# tick-mk-4_7.net
KiCad netlist of a schematic drawn in EAGLE
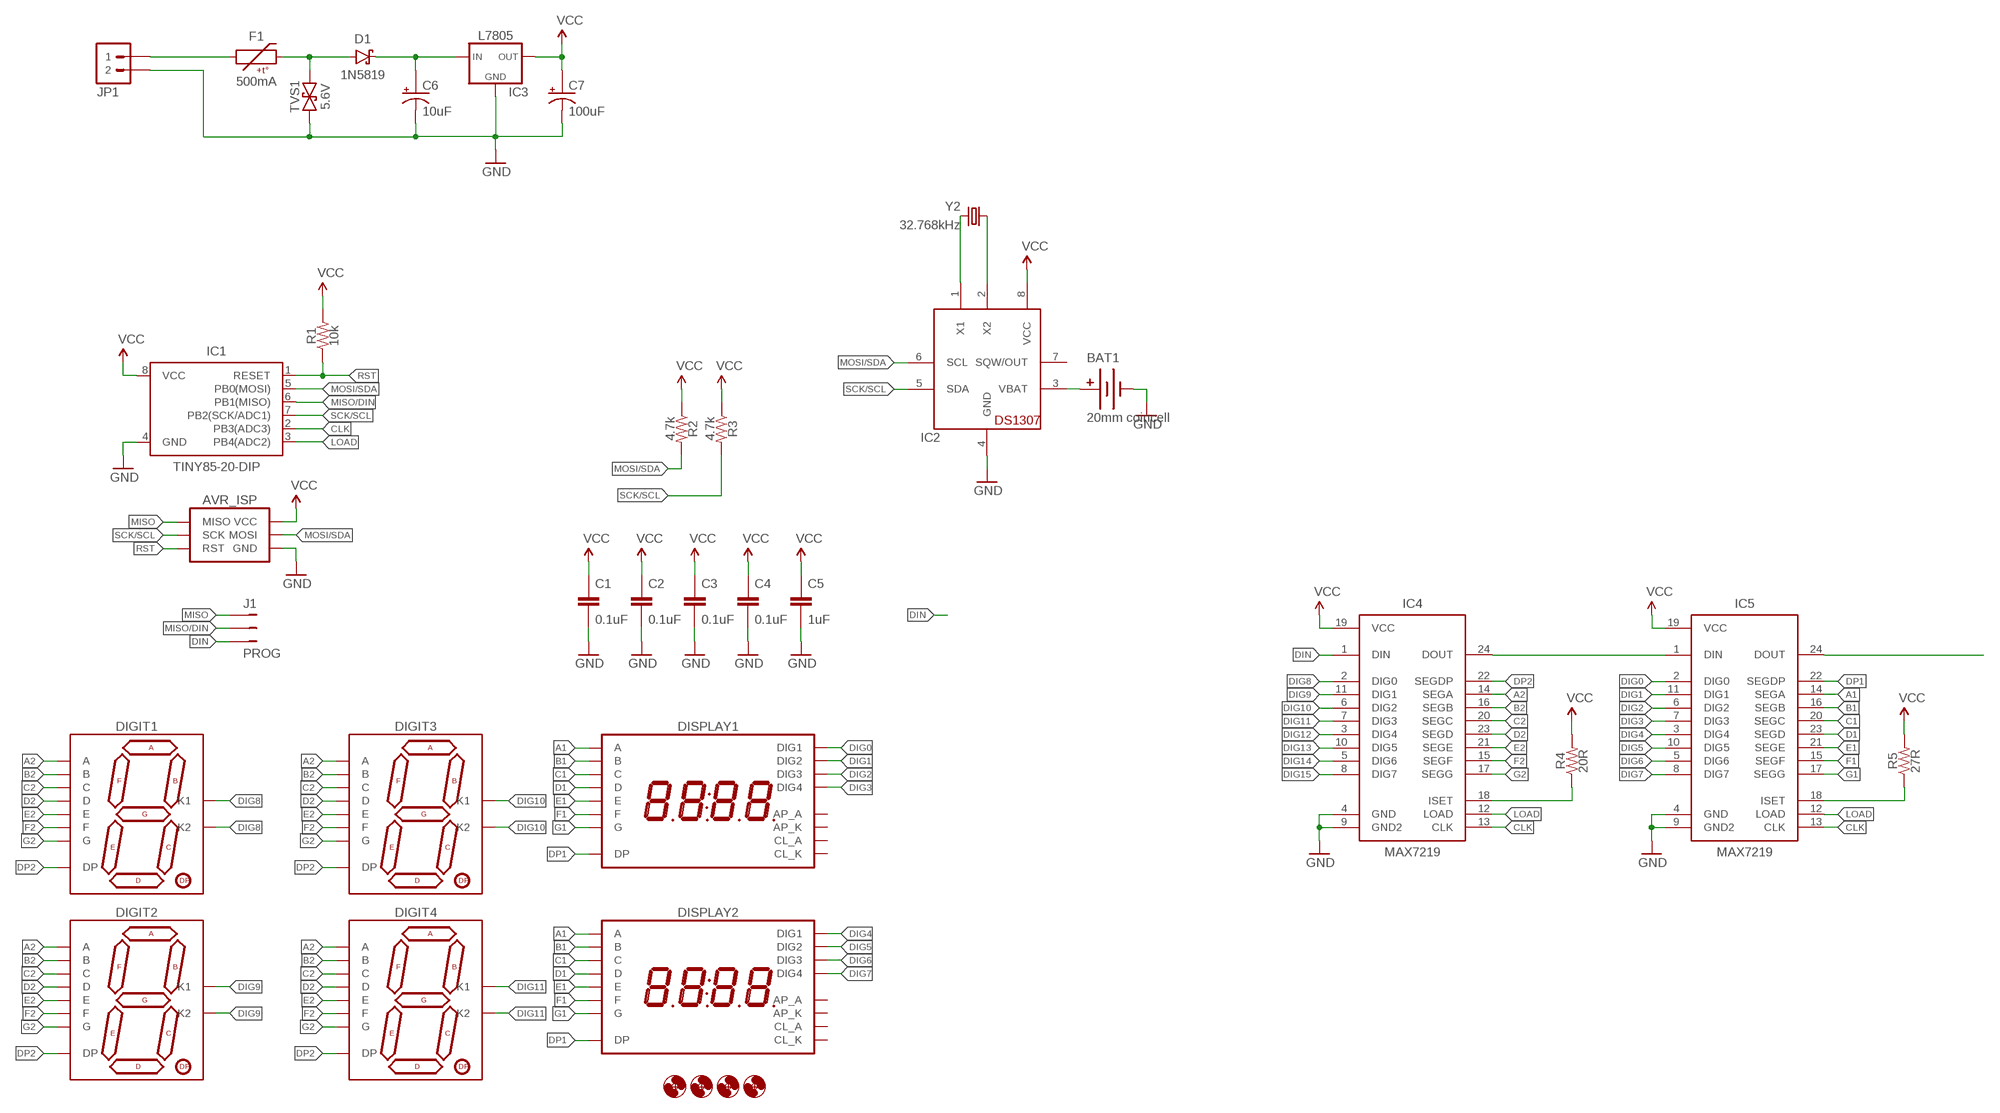
[diagram p0: schematic, sheet 1]

(export (version "E")
  (design (tool "Eeschema 10.0.6"))
  (components
    (comp (ref "AVR_ISP")
      (value "AVR_SPI_PRG_6PTH")
      (footprint "eagle-import:2X3")
      (libsource (lib "eagle-import") (part "AVR_SPI_PRG_6PTH"))
    )
    (comp (ref "BAT1")
      (value "20mm coincell")
      (footprint "eagle-import:BATTCON_20MM_MINE")
      (libsource (lib "eagle-import") (part "BATTERY20MMSMD-MINE"))
    )
    (comp (ref "C1")
      (value "0.1uF")
      (footprint "eagle-import:C025-024X044")
      (libsource (lib "eagle-import") (part "CAPACITOR-CERAMIC025-024X044"))
    )
    (comp (ref "C2")
      (value "0.1uF")
      (footprint "eagle-import:C025-024X044")
      (libsource (lib "eagle-import") (part "CAPACITOR-CERAMIC025-024X044"))
    )
    (comp (ref "C3")
      (value "0.1uF")
      (footprint "eagle-import:C025-024X044")
      (libsource (lib "eagle-import") (part "CAPACITOR-CERAMIC025-024X044"))
    )
    (comp (ref "C4")
      (value "0.1uF")
      (footprint "eagle-import:C025-024X044")
      (libsource (lib "eagle-import") (part "CAPACITOR-CERAMIC025-024X044"))
    )
    (comp (ref "C5")
      (value "1uF")
      (footprint "eagle-import:C025-024X044")
      (libsource (lib "eagle-import") (part "CAPACITOR-CERAMIC025-024X044"))
    )
    (comp (ref "C6")
      (value "10uF")
      (footprint "eagle-import:E2-5")
      (libsource (lib "eagle-import") (part "CAPACITOR-POLARIZEDE2-5"))
    )
    (comp (ref "C7")
      (value "100uF")
      (footprint "eagle-import:E2,5-6")
      (libsource (lib "eagle-import") (part "CAPACITOR-POLARIZEDE2.5-6"))
    )
    (comp (ref "D1")
      (value "1N5819")
      (footprint "eagle-import:DIODE-10.16MM")
      (libsource (lib "eagle-import") (part "DIODE-SCHOTTKYPTH-10.16MM"))
    )
    (comp (ref "DIGIT1")
      (value "7SEG_1DIGPTH-25.4MM-BARE")
      (footprint "eagle-import:7SEG_1DIG_25.4MM_NOSILK")
      (libsource (lib "eagle-import") (part "7SEG_1DIGPTH-25.4MM-BARE"))
    )
    (comp (ref "DIGIT2")
      (value "7SEG_1DIGPTH-25.4MM-BARE")
      (footprint "eagle-import:7SEG_1DIG_25.4MM_NOSILK")
      (libsource (lib "eagle-import") (part "7SEG_1DIGPTH-25.4MM-BARE"))
    )
    (comp (ref "DIGIT3")
      (value "7SEG_1DIGPTH-25.4MM-BARE")
      (footprint "eagle-import:7SEG_1DIG_25.4MM_NOSILK")
      (libsource (lib "eagle-import") (part "7SEG_1DIGPTH-25.4MM-BARE"))
    )
    (comp (ref "DIGIT4")
      (value "7SEG_1DIGPTH-25.4MM-BARE")
      (footprint "eagle-import:7SEG_1DIG_25.4MM_NOSILK")
      (libsource (lib "eagle-import") (part "7SEG_1DIGPTH-25.4MM-BARE"))
    )
    (comp (ref "DISPLAY1")
      (value "7SEG_4DIGIT_COLON_APOS")
      (footprint "eagle-import:7SEG_4DIG_10MM")
      (libsource (lib "eagle-import") (part "7SEG_4DIGIT_COLON_APOS"))
    )
    (comp (ref "DISPLAY2")
      (value "7SEG_4DIGIT_COLON_APOS")
      (footprint "eagle-import:7SEG_4DIG_10MM")
      (libsource (lib "eagle-import") (part "7SEG_4DIGIT_COLON_APOS"))
    )
    (comp (ref "F1")
      (value "500mA")
      (footprint "eagle-import:PTC-PTH-5.08MM")
      (libsource (lib "eagle-import") (part "PTCPTH-5.08MM"))
    )
    (comp (ref "H1")
      (value "HOLE#2")
      (footprint "eagle-import:HOLE-#2")
      (libsource (lib "eagle-import") (part "HOLE#2"))
    )
    (comp (ref "H2")
      (value "HOLE#2")
      (footprint "eagle-import:HOLE-#2")
      (libsource (lib "eagle-import") (part "HOLE#2"))
    )
    (comp (ref "H3")
      (value "HOLE#2")
      (footprint "eagle-import:HOLE-#2")
      (libsource (lib "eagle-import") (part "HOLE#2"))
    )
    (comp (ref "H4")
      (value "HOLE#2")
      (footprint "eagle-import:HOLE-#2")
      (libsource (lib "eagle-import") (part "HOLE#2"))
    )
    (comp (ref "IC1")
      (value "TINY85-20-DIP")
      (footprint "eagle-import:DIP08")
      (libsource (lib "eagle-import") (part "ATTINY45TINY85-20-DIP"))
    )
    (comp (ref "IC2")
      (value "DS1307")
      (footprint "eagle-import:DIL08")
      (libsource (lib "eagle-import") (part "DS1307"))
    )
    (comp (ref "IC3")
      (value "L7805")
      (footprint "eagle-import:TO220-IGO-THERMPAD")
      (libsource (lib "eagle-import") (part "V_REG_78XXTO-220-THERMPAD"))
    )
    (comp (ref "IC4")
      (value "MAX7219")
      (footprint "eagle-import:SO24W")
      (libsource (lib "eagle-import") (part "MAX7219SOIC-W"))
    )
    (comp (ref "IC5")
      (value "MAX7219")
      (footprint "eagle-import:SO24W")
      (libsource (lib "eagle-import") (part "MAX7219SOIC-W"))
    )
    (comp (ref "J1")
      (value "PROG")
      (footprint "eagle-import:1X03")
      (libsource (lib "eagle-import") (part "JUMPER-PTH-3-NO"))
    )
    (comp (ref "JP1")
      (value "M02JST-XH-VERT")
      (footprint "eagle-import:JST-2-XH-VERT-PTH")
      (libsource (lib "eagle-import") (part "M02JST-XH-VERT"))
    )
    (comp (ref "R1")
      (value "10k")
      (footprint "eagle-import:RESISTOR-AXIAL-PTH-7.62MM")
      (libsource (lib "eagle-import") (part "RESISTORPTH-AXIAL-7.62MM"))
    )
    (comp (ref "R2")
      (value "4.7k")
      (footprint "eagle-import:RESISTOR-AXIAL-PTH-7.62MM")
      (libsource (lib "eagle-import") (part "RESISTORPTH-AXIAL-7.62MM"))
    )
    (comp (ref "R3")
      (value "4.7k")
      (footprint "eagle-import:RESISTOR-AXIAL-PTH-7.62MM")
      (libsource (lib "eagle-import") (part "RESISTORPTH-AXIAL-7.62MM"))
    )
    (comp (ref "R4")
      (value "20R")
      (footprint "eagle-import:RESISTOR-AXIAL-PTH-7.62MM")
      (libsource (lib "eagle-import") (part "RESISTORPTH-AXIAL-7.62MM"))
    )
    (comp (ref "R5")
      (value "27R")
      (footprint "eagle-import:RESISTOR-AXIAL-PTH-7.62MM")
      (libsource (lib "eagle-import") (part "RESISTORPTH-AXIAL-7.62MM"))
    )
    (comp (ref "TVS1")
      (value "5.6V")
      (footprint "eagle-import:DO-41-TVS-BI-10.16MM")
      (libsource (lib "eagle-import") (part "TVSDO-41-10.16MM"))
    )
    (comp (ref "Y2")
      (value "32.768kHz")
      (footprint "eagle-import:TC26H")
      (libsource (lib "eagle-import") (part "CRYSTALTC26H"))
    )
  )
  (nets
    (net (code "1") (name "A1") (class "Default")
      (node (ref "DISPLAY1") (pin "14") (pinfunction "A_14") (pintype "passive"))
      (node (ref "DISPLAY2") (pin "14") (pinfunction "A_14") (pintype "passive"))
      (node (ref "IC5") (pin "14") (pinfunction "SEGA_14") (pintype "bidirectional"))
    )
    (net (code "2") (name "A2") (class "Default")
      (node (ref "DIGIT1") (pin "7") (pinfunction "A_7") (pintype "bidirectional"))
      (node (ref "DIGIT2") (pin "7") (pinfunction "A_7") (pintype "bidirectional"))
      (node (ref "DIGIT3") (pin "7") (pinfunction "A_7") (pintype "bidirectional"))
      (node (ref "DIGIT4") (pin "7") (pinfunction "A_7") (pintype "bidirectional"))
      (node (ref "IC4") (pin "14") (pinfunction "SEGA_14") (pintype "bidirectional"))
    )
    (net (code "3") (name "B1") (class "Default")
      (node (ref "DISPLAY1") (pin "16") (pinfunction "B_16") (pintype "passive"))
      (node (ref "DISPLAY2") (pin "16") (pinfunction "B_16") (pintype "passive"))
      (node (ref "IC5") (pin "16") (pinfunction "SEGB_16") (pintype "bidirectional"))
    )
    (net (code "4") (name "B2") (class "Default")
      (node (ref "DIGIT1") (pin "6") (pinfunction "B_6") (pintype "bidirectional"))
      (node (ref "DIGIT2") (pin "6") (pinfunction "B_6") (pintype "bidirectional"))
      (node (ref "DIGIT3") (pin "6") (pinfunction "B_6") (pintype "bidirectional"))
      (node (ref "DIGIT4") (pin "6") (pinfunction "B_6") (pintype "bidirectional"))
      (node (ref "IC4") (pin "16") (pinfunction "SEGB_16") (pintype "bidirectional"))
    )
    (net (code "5") (name "C1") (class "Default")
      (node (ref "DISPLAY1") (pin "13") (pinfunction "C_13") (pintype "passive"))
      (node (ref "DISPLAY2") (pin "13") (pinfunction "C_13") (pintype "passive"))
      (node (ref "IC5") (pin "20") (pinfunction "SEGC_20") (pintype "bidirectional"))
    )
    (net (code "6") (name "C2") (class "Default")
      (node (ref "DIGIT1") (pin "4") (pinfunction "C_4") (pintype "bidirectional"))
      (node (ref "DIGIT2") (pin "4") (pinfunction "C_4") (pintype "bidirectional"))
      (node (ref "DIGIT3") (pin "4") (pinfunction "C_4") (pintype "bidirectional"))
      (node (ref "DIGIT4") (pin "4") (pinfunction "C_4") (pintype "bidirectional"))
      (node (ref "IC4") (pin "20") (pinfunction "SEGC_20") (pintype "bidirectional"))
    )
    (net (code "7") (name "CLK") (class "Default")
      (node (ref "IC1") (pin "2") (pinfunction "PB3(ADC3)_2") (pintype "bidirectional"))
      (node (ref "IC4") (pin "13") (pinfunction "CLK_13") (pintype "bidirectional"))
      (node (ref "IC5") (pin "13") (pinfunction "CLK_13") (pintype "bidirectional"))
    )
    (net (code "8") (name "D1") (class "Default")
      (node (ref "DISPLAY1") (pin "3") (pinfunction "D_3") (pintype "passive"))
      (node (ref "DISPLAY2") (pin "3") (pinfunction "D_3") (pintype "passive"))
      (node (ref "IC5") (pin "23") (pinfunction "SEGD_23") (pintype "bidirectional"))
    )
    (net (code "9") (name "D2") (class "Default")
      (node (ref "DIGIT1") (pin "2") (pinfunction "D_2") (pintype "bidirectional"))
      (node (ref "DIGIT2") (pin "2") (pinfunction "D_2") (pintype "bidirectional"))
      (node (ref "DIGIT3") (pin "2") (pinfunction "D_2") (pintype "bidirectional"))
      (node (ref "DIGIT4") (pin "2") (pinfunction "D_2") (pintype "bidirectional"))
      (node (ref "IC4") (pin "23") (pinfunction "SEGD_23") (pintype "bidirectional"))
    )
    (net (code "10") (name "DIG0") (class "Default")
      (node (ref "DISPLAY1") (pin "1") (pinfunction "DIG1_1") (pintype "passive"))
      (node (ref "IC5") (pin "2") (pinfunction "DIG0_2") (pintype "bidirectional"))
    )
    (net (code "11") (name "DIG1") (class "Default")
      (node (ref "DISPLAY1") (pin "2") (pinfunction "DIG2_2") (pintype "passive"))
      (node (ref "IC5") (pin "11") (pinfunction "DIG1_11") (pintype "bidirectional"))
    )
    (net (code "12") (name "DIG2") (class "Default")
      (node (ref "DISPLAY1") (pin "6") (pinfunction "DIG3_6") (pintype "passive"))
      (node (ref "IC5") (pin "6") (pinfunction "DIG2_6") (pintype "bidirectional"))
    )
    (net (code "13") (name "DIG3") (class "Default")
      (node (ref "DISPLAY1") (pin "8") (pinfunction "DIG4_8") (pintype "passive"))
      (node (ref "IC5") (pin "7") (pinfunction "DIG3_7") (pintype "bidirectional"))
    )
    (net (code "14") (name "DIG4") (class "Default")
      (node (ref "DISPLAY2") (pin "1") (pinfunction "DIG1_1") (pintype "passive"))
      (node (ref "IC5") (pin "3") (pinfunction "DIG4_3") (pintype "bidirectional"))
    )
    (net (code "15") (name "DIG5") (class "Default")
      (node (ref "DISPLAY2") (pin "2") (pinfunction "DIG2_2") (pintype "passive"))
      (node (ref "IC5") (pin "10") (pinfunction "DIG5_10") (pintype "bidirectional"))
    )
    (net (code "16") (name "DIG6") (class "Default")
      (node (ref "DISPLAY2") (pin "6") (pinfunction "DIG3_6") (pintype "passive"))
      (node (ref "IC5") (pin "5") (pinfunction "DIG6_5") (pintype "bidirectional"))
    )
    (net (code "17") (name "DIG7") (class "Default")
      (node (ref "DISPLAY2") (pin "8") (pinfunction "DIG4_8") (pintype "passive"))
      (node (ref "IC5") (pin "8") (pinfunction "DIG7_8") (pintype "bidirectional"))
    )
    (net (code "18") (name "DIG8") (class "Default")
      (node (ref "DIGIT1") (pin "3") (pinfunction "K1_3") (pintype "bidirectional"))
      (node (ref "DIGIT1") (pin "8") (pinfunction "K2_8") (pintype "bidirectional"))
      (node (ref "IC4") (pin "2") (pinfunction "DIG0_2") (pintype "bidirectional"))
    )
    (net (code "19") (name "DIG9") (class "Default")
      (node (ref "DIGIT2") (pin "3") (pinfunction "K1_3") (pintype "bidirectional"))
      (node (ref "DIGIT2") (pin "8") (pinfunction "K2_8") (pintype "bidirectional"))
      (node (ref "IC4") (pin "11") (pinfunction "DIG1_11") (pintype "bidirectional"))
    )
    (net (code "20") (name "DIG10") (class "Default")
      (node (ref "DIGIT3") (pin "3") (pinfunction "K1_3") (pintype "bidirectional"))
      (node (ref "DIGIT3") (pin "8") (pinfunction "K2_8") (pintype "bidirectional"))
      (node (ref "IC4") (pin "6") (pinfunction "DIG2_6") (pintype "bidirectional"))
    )
    (net (code "21") (name "DIG11") (class "Default")
      (node (ref "DIGIT4") (pin "3") (pinfunction "K1_3") (pintype "bidirectional"))
      (node (ref "DIGIT4") (pin "8") (pinfunction "K2_8") (pintype "bidirectional"))
      (node (ref "IC4") (pin "7") (pinfunction "DIG3_7") (pintype "bidirectional"))
    )
    (net (code "22") (name "DIG12") (class "Default")
      (node (ref "IC4") (pin "3") (pinfunction "DIG4_3") (pintype "bidirectional"))
    )
    (net (code "23") (name "DIG13") (class "Default")
      (node (ref "IC4") (pin "10") (pinfunction "DIG5_10") (pintype "bidirectional"))
    )
    (net (code "24") (name "DIG14") (class "Default")
      (node (ref "IC4") (pin "5") (pinfunction "DIG6_5") (pintype "bidirectional"))
    )
    (net (code "25") (name "DIG15") (class "Default")
      (node (ref "IC4") (pin "8") (pinfunction "DIG7_8") (pintype "bidirectional"))
    )
    (net (code "26") (name "DIN") (class "Default")
      (node (ref "IC4") (pin "1") (pinfunction "DIN_1") (pintype "bidirectional"))
      (node (ref "J1") (pin "3") (pinfunction "3_3") (pintype "passive"))
    )
    (net (code "27") (name "DP1") (class "Default")
      (node (ref "DISPLAY1") (pin "7") (pinfunction "DP_7") (pintype "passive"))
      (node (ref "DISPLAY2") (pin "7") (pinfunction "DP_7") (pintype "passive"))
      (node (ref "IC5") (pin "22") (pinfunction "SEGDP_22") (pintype "bidirectional"))
    )
    (net (code "28") (name "DP2") (class "Default")
      (node (ref "DIGIT1") (pin "5") (pinfunction "DP_5") (pintype "bidirectional"))
      (node (ref "DIGIT2") (pin "5") (pinfunction "DP_5") (pintype "bidirectional"))
      (node (ref "DIGIT3") (pin "5") (pinfunction "DP_5") (pintype "bidirectional"))
      (node (ref "DIGIT4") (pin "5") (pinfunction "DP_5") (pintype "bidirectional"))
      (node (ref "IC4") (pin "22") (pinfunction "SEGDP_22") (pintype "bidirectional"))
    )
    (net (code "29") (name "E1") (class "Default")
      (node (ref "DISPLAY1") (pin "5") (pinfunction "E_5") (pintype "passive"))
      (node (ref "DISPLAY2") (pin "5") (pinfunction "E_5") (pintype "passive"))
      (node (ref "IC5") (pin "21") (pinfunction "SEGE_21") (pintype "bidirectional"))
    )
    (net (code "30") (name "E2") (class "Default")
      (node (ref "DIGIT1") (pin "1") (pinfunction "E_1") (pintype "bidirectional"))
      (node (ref "DIGIT2") (pin "1") (pinfunction "E_1") (pintype "bidirectional"))
      (node (ref "DIGIT3") (pin "1") (pinfunction "E_1") (pintype "bidirectional"))
      (node (ref "DIGIT4") (pin "1") (pinfunction "E_1") (pintype "bidirectional"))
      (node (ref "IC4") (pin "21") (pinfunction "SEGE_21") (pintype "bidirectional"))
    )
    (net (code "31") (name "F1") (class "Default")
      (node (ref "DISPLAY1") (pin "11") (pinfunction "F_11") (pintype "passive"))
      (node (ref "DISPLAY2") (pin "11") (pinfunction "F_11") (pintype "passive"))
      (node (ref "IC5") (pin "15") (pinfunction "SEGF_15") (pintype "bidirectional"))
    )
    (net (code "32") (name "F2") (class "Default")
      (node (ref "DIGIT1") (pin "9") (pinfunction "F_9") (pintype "bidirectional"))
      (node (ref "DIGIT2") (pin "9") (pinfunction "F_9") (pintype "bidirectional"))
      (node (ref "DIGIT3") (pin "9") (pinfunction "F_9") (pintype "bidirectional"))
      (node (ref "DIGIT4") (pin "9") (pinfunction "F_9") (pintype "bidirectional"))
      (node (ref "IC4") (pin "15") (pinfunction "SEGF_15") (pintype "bidirectional"))
    )
    (net (code "33") (name "G1") (class "Default")
      (node (ref "DISPLAY1") (pin "15") (pinfunction "G_15") (pintype "passive"))
      (node (ref "DISPLAY2") (pin "15") (pinfunction "G_15") (pintype "passive"))
      (node (ref "IC5") (pin "17") (pinfunction "SEGG_17") (pintype "bidirectional"))
    )
    (net (code "34") (name "G2") (class "Default")
      (node (ref "DIGIT1") (pin "10") (pinfunction "G_10") (pintype "bidirectional"))
      (node (ref "DIGIT2") (pin "10") (pinfunction "G_10") (pintype "bidirectional"))
      (node (ref "DIGIT3") (pin "10") (pinfunction "G_10") (pintype "bidirectional"))
      (node (ref "DIGIT4") (pin "10") (pinfunction "G_10") (pintype "bidirectional"))
      (node (ref "IC4") (pin "17") (pinfunction "SEGG_17") (pintype "bidirectional"))
    )
    (net (code "35") (name "GND") (class "Default")
      (node (ref "AVR_ISP") (pin "6") (pinfunction "GND_6") (pintype "passive"))
      (node (ref "BAT1") (pin "BOTTOM") (pinfunction "-_BOTTOM") (pintype "power_in"))
      (node (ref "C1") (pin "2") (pinfunction "2_2") (pintype "passive"))
      (node (ref "C2") (pin "2") (pinfunction "2_2") (pintype "passive"))
      (node (ref "C3") (pin "2") (pinfunction "2_2") (pintype "passive"))
      (node (ref "C4") (pin "2") (pinfunction "2_2") (pintype "passive"))
      (node (ref "C5") (pin "2") (pinfunction "2_2") (pintype "passive"))
      (node (ref "C6") (pin "-") (pinfunction "-_-") (pintype "passive"))
      (node (ref "C7") (pin "-") (pinfunction "-_-") (pintype "passive"))
      (node (ref "IC1") (pin "4") (pinfunction "GND_4") (pintype "bidirectional"))
      (node (ref "IC2") (pin "4") (pinfunction "GND_4") (pintype "power_in"))
      (node (ref "IC3") (pin "4") (pinfunction "GND_4") (pintype "bidirectional"))
      (node (ref "IC3") (pin "GND") (pinfunction "GND_GND") (pintype "bidirectional"))
      (node (ref "IC4") (pin "4") (pinfunction "GND_4") (pintype "bidirectional"))
      (node (ref "IC4") (pin "9") (pinfunction "GND2_9") (pintype "bidirectional"))
      (node (ref "IC5") (pin "4") (pinfunction "GND_4") (pintype "bidirectional"))
      (node (ref "IC5") (pin "9") (pinfunction "GND2_9") (pintype "bidirectional"))
      (node (ref "JP1") (pin "2") (pinfunction "2_2") (pintype "passive"))
      (node (ref "TVS1") (pin "P$1") (pinfunction "1_P$1") (pintype "passive"))
    )
    (net (code "36") (name "LOAD") (class "Default")
      (node (ref "IC1") (pin "3") (pinfunction "PB4(ADC2)_3") (pintype "bidirectional"))
      (node (ref "IC4") (pin "12") (pinfunction "LOAD_12") (pintype "bidirectional"))
      (node (ref "IC5") (pin "12") (pinfunction "LOAD_12") (pintype "bidirectional"))
    )
    (net (code "37") (name "MISO") (class "Default")
      (node (ref "AVR_ISP") (pin "1") (pinfunction "MISO_1") (pintype "passive"))
      (node (ref "J1") (pin "1") (pinfunction "1_1") (pintype "passive"))
    )
    (net (code "38") (name "MISO{slash}DIN") (class "Default")
      (node (ref "IC1") (pin "6") (pinfunction "PB1(MISO)_6") (pintype "bidirectional"))
      (node (ref "J1") (pin "2") (pinfunction "2_2") (pintype "passive"))
    )
    (net (code "39") (name "MOSI{slash}SDA") (class "Default")
      (node (ref "AVR_ISP") (pin "4") (pinfunction "MOSI_4") (pintype "passive"))
      (node (ref "IC1") (pin "5") (pinfunction "PB0(MOSI)_5") (pintype "bidirectional"))
      (node (ref "IC2") (pin "6") (pinfunction "SCL_6") (pintype "bidirectional"))
      (node (ref "R2") (pin "P$2") (pinfunction "2_P$2") (pintype "passive"))
    )
    (net (code "40") (name "Net-(C6-Pad+)") (class "Default")
      (node (ref "C6") (pin "+") (pinfunction "+_+") (pintype "passive"))
      (node (ref "D1") (pin "C") (pinfunction "C_C") (pintype "passive"))
      (node (ref "IC3") (pin "IN") (pinfunction "IN_IN") (pintype "bidirectional"))
    )
    (net (code "41") (name "Net-(F1-1)") (class "Default")
      (node (ref "F1") (pin "P$1") (pinfunction "1_P$1") (pintype "passive"))
      (node (ref "JP1") (pin "1") (pinfunction "1_1") (pintype "passive"))
    )
    (net (code "42") (name "Net-(F1-2)") (class "Default")
      (node (ref "D1") (pin "A") (pinfunction "A_A") (pintype "passive"))
      (node (ref "F1") (pin "P$2") (pinfunction "2_P$2") (pintype "passive"))
      (node (ref "TVS1") (pin "P$2") (pinfunction "2_P$2") (pintype "passive"))
    )
    (net (code "43") (name "Net-(IC2-VBAT)") (class "Default")
      (node (ref "BAT1") (pin "TOP@1") (pinfunction "+_TOP@1") (pintype "power_in"))
      (node (ref "BAT1") (pin "TOP@2") (pinfunction "+_TOP@2") (pintype "power_in"))
      (node (ref "IC2") (pin "3") (pinfunction "VBAT_3") (pintype "power_in"))
    )
    (net (code "44") (name "Net-(IC2-X1)") (class "Default")
      (node (ref "IC2") (pin "1") (pinfunction "X1_1") (pintype "passive"))
      (node (ref "Y2") (pin "2") (pinfunction "2_2") (pintype "passive"))
    )
    (net (code "45") (name "Net-(IC2-X2)") (class "Default")
      (node (ref "IC2") (pin "2") (pinfunction "X2_2") (pintype "passive"))
      (node (ref "Y2") (pin "1") (pinfunction "1_1") (pintype "passive"))
    )
    (net (code "46") (name "Net-(IC4-DOUT)") (class "Default")
      (node (ref "IC4") (pin "24") (pinfunction "DOUT_24") (pintype "bidirectional"))
      (node (ref "IC5") (pin "1") (pinfunction "DIN_1") (pintype "bidirectional"))
    )
    (net (code "47") (name "Net-(IC4-ISET)") (class "Default")
      (node (ref "IC4") (pin "18") (pinfunction "ISET_18") (pintype "bidirectional"))
      (node (ref "R4") (pin "P$1") (pinfunction "1_P$1") (pintype "passive"))
    )
    (net (code "48") (name "Net-(IC5-ISET)") (class "Default")
      (node (ref "IC5") (pin "18") (pinfunction "ISET_18") (pintype "bidirectional"))
      (node (ref "R5") (pin "P$1") (pinfunction "1_P$1") (pintype "passive"))
    )
    (net (code "49") (name "RST") (class "Default")
      (node (ref "AVR_ISP") (pin "5") (pinfunction "RST_5") (pintype "passive"))
      (node (ref "IC1") (pin "1") (pinfunction "RESET_1") (pintype "bidirectional"))
      (node (ref "R1") (pin "P$1") (pinfunction "1_P$1") (pintype "passive"))
    )
    (net (code "50") (name "SCK{slash}SCL") (class "Default")
      (node (ref "AVR_ISP") (pin "3") (pinfunction "SCK_3") (pintype "passive"))
      (node (ref "IC1") (pin "7") (pinfunction "PB2(SCK/ADC1)_7") (pintype "bidirectional"))
      (node (ref "IC2") (pin "5") (pinfunction "SDA_5") (pintype "bidirectional"))
      (node (ref "R3") (pin "P$2") (pinfunction "2_P$2") (pintype "passive"))
    )
    (net (code "51") (name "VCC") (class "Default")
      (node (ref "AVR_ISP") (pin "2") (pinfunction "VCC_2") (pintype "passive"))
      (node (ref "C1") (pin "1") (pinfunction "1_1") (pintype "passive"))
      (node (ref "C2") (pin "1") (pinfunction "1_1") (pintype "passive"))
      (node (ref "C3") (pin "1") (pinfunction "1_1") (pintype "passive"))
      (node (ref "C4") (pin "1") (pinfunction "1_1") (pintype "passive"))
      (node (ref "C5") (pin "1") (pinfunction "1_1") (pintype "passive"))
      (node (ref "C7") (pin "+") (pinfunction "+_+") (pintype "passive"))
      (node (ref "IC1") (pin "8") (pinfunction "VCC_8") (pintype "bidirectional"))
      (node (ref "IC2") (pin "8") (pinfunction "VCC_8") (pintype "power_in"))
      (node (ref "IC3") (pin "OUT") (pinfunction "OUT_OUT") (pintype "bidirectional"))
      (node (ref "IC4") (pin "19") (pinfunction "VCC_19") (pintype "bidirectional"))
      (node (ref "IC5") (pin "19") (pinfunction "VCC_19") (pintype "bidirectional"))
      (node (ref "R1") (pin "P$2") (pinfunction "2_P$2") (pintype "passive"))
      (node (ref "R2") (pin "P$1") (pinfunction "1_P$1") (pintype "passive"))
      (node (ref "R3") (pin "P$1") (pinfunction "1_P$1") (pintype "passive"))
      (node (ref "R4") (pin "P$2") (pinfunction "2_P$2") (pintype "passive"))
      (node (ref "R5") (pin "P$2") (pinfunction "2_P$2") (pintype "passive"))
    )
    (net (code "52") (name "unconnected-(DISPLAY1-AP_A-Pad10)") (class "Default")
      (node (ref "DISPLAY1") (pin "10") (pinfunction "AP_A_10") (pintype "bidirectional"))
    )
    (net (code "53") (name "unconnected-(DISPLAY1-AP_K-Pad9)") (class "Default")
      (node (ref "DISPLAY1") (pin "9") (pinfunction "AP_K_9") (pintype "bidirectional"))
    )
    (net (code "54") (name "unconnected-(DISPLAY1-CL_A-Pad4)") (class "Default")
      (node (ref "DISPLAY1") (pin "4") (pinfunction "CL_A_4") (pintype "passive"))
    )
    (net (code "55") (name "unconnected-(DISPLAY1-CL_K-Pad12)") (class "Default")
      (node (ref "DISPLAY1") (pin "12") (pinfunction "CL_K_12") (pintype "passive"))
    )
    (net (code "56") (name "unconnected-(DISPLAY2-AP_A-Pad10)") (class "Default")
      (node (ref "DISPLAY2") (pin "10") (pinfunction "AP_A_10") (pintype "bidirectional"))
    )
    (net (code "57") (name "unconnected-(DISPLAY2-AP_K-Pad9)") (class "Default")
      (node (ref "DISPLAY2") (pin "9") (pinfunction "AP_K_9") (pintype "bidirectional"))
    )
    (net (code "58") (name "unconnected-(DISPLAY2-CL_A-Pad4)") (class "Default")
      (node (ref "DISPLAY2") (pin "4") (pinfunction "CL_A_4") (pintype "passive"))
    )
    (net (code "59") (name "unconnected-(DISPLAY2-CL_K-Pad12)") (class "Default")
      (node (ref "DISPLAY2") (pin "12") (pinfunction "CL_K_12") (pintype "passive"))
    )
    (net (code "60") (name "unconnected-(IC2-SQW{slash}OUT-Pad7)") (class "Default")
      (node (ref "IC2") (pin "7") (pinfunction "SQW/OUT_7") (pintype "bidirectional"))
    )
    (net (code "61") (name "unconnected-(IC5-DOUT-Pad24)") (class "Default")
      (node (ref "IC5") (pin "24") (pinfunction "DOUT_24") (pintype "bidirectional"))
    )
  )
)
